# RH003_1.net
KiCad netlist of a schematic drawn in EAGLE
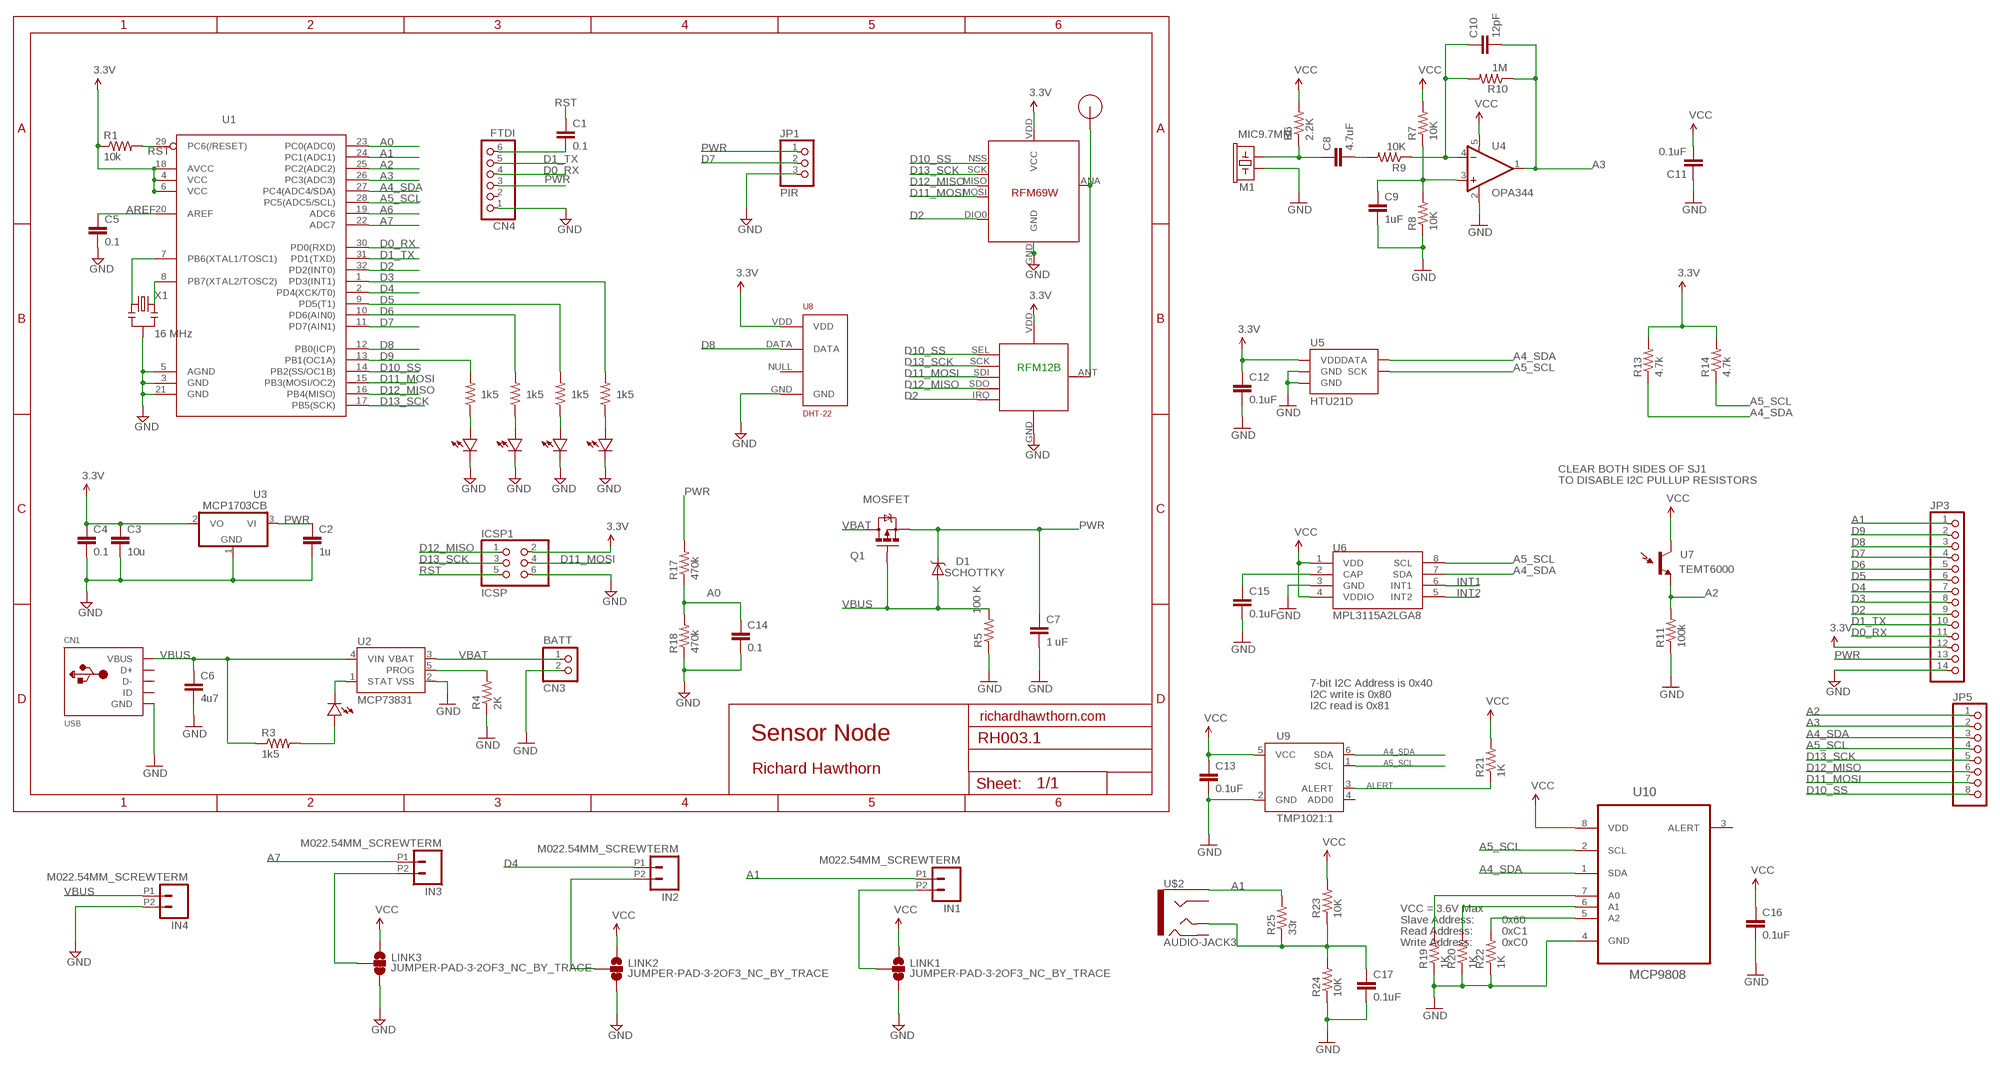
[diagram p0: schematic, sheet 1]

(export (version "E")
  (design (tool "Eeschema 10.0.6"))
  (components
    (comp (ref "C1")
      (value "0.1")
      (footprint "eagle-import:0603-CAP")
      (libsource (lib "eagle-import") (part "CAP0603-CAP"))
    )
    (comp (ref "C2")
      (value "1u")
      (footprint "eagle-import:0603-CAP")
      (libsource (lib "eagle-import") (part "CAP0603-CAP"))
    )
    (comp (ref "C3")
      (value "10u")
      (footprint "eagle-import:0805-CAP")
      (libsource (lib "eagle-import") (part "CAP0805-CAP"))
    )
    (comp (ref "C4")
      (value "0.1")
      (footprint "eagle-import:0603-CAP")
      (libsource (lib "eagle-import") (part "CAP0603-CAP"))
    )
    (comp (ref "C5")
      (value "0.1")
      (footprint "eagle-import:0603-CAP")
      (libsource (lib "eagle-import") (part "CAP0603-CAP"))
    )
    (comp (ref "C6")
      (value "4u7")
      (footprint "eagle-import:0603-CAP")
      (libsource (lib "eagle-import") (part "SparkFun_CAP0603-CAP"))
    )
    (comp (ref "C7")
      (value "1 uF")
      (footprint "eagle-import:0805")
      (libsource (lib "eagle-import") (part "SparkFun-Capacitors_CAP0805"))
    )
    (comp (ref "C8")
      (value "4.7uF")
      (footprint "eagle-import:0805")
      (libsource (lib "eagle-import") (part "SparkFun_CAP0805"))
    )
    (comp (ref "C9")
      (value "1uF")
      (footprint "eagle-import:0805")
      (libsource (lib "eagle-import") (part "SparkFun_CAP0805"))
    )
    (comp (ref "C10")
      (value "12pF")
      (footprint "eagle-import:0805")
      (libsource (lib "eagle-import") (part "SparkFun_CAP0805"))
    )
    (comp (ref "C11")
      (value "0.1uF")
      (footprint "eagle-import:0805")
      (libsource (lib "eagle-import") (part "SparkFun_CAP0805"))
    )
    (comp (ref "C12")
      (value "0.1uF")
      (footprint "eagle-import:0805")
      (libsource (lib "eagle-import") (part "SparkFun_CAP0805"))
    )
    (comp (ref "C13")
      (value "0.1uF")
      (footprint "eagle-import:0603-CAP")
      (libsource (lib "eagle-import") (part "SparkFun_CAP0603-CAP"))
    )
    (comp (ref "C14")
      (value "0.1")
      (footprint "eagle-import:0603-CAP")
      (libsource (lib "eagle-import") (part "CAP0603-CAP"))
    )
    (comp (ref "C15")
      (value "0.1uF")
      (footprint "eagle-import:0805")
      (libsource (lib "eagle-import") (part "SparkFun_CAP0805"))
    )
    (comp (ref "C16")
      (value "0.1uF")
      (footprint "eagle-import:0603-CAP")
      (libsource (lib "eagle-import") (part "SparkFun_CAP0603-CAP"))
    )
    (comp (ref "C17")
      (value "0.1uF")
      (footprint "eagle-import:0603-CAP")
      (libsource (lib "eagle-import") (part "SparkFun_CAP0603-CAP"))
    )
    (comp (ref "CN1")
      (value "USB")
      (footprint "eagle-import:USB-MINIB")
      (libsource (lib "eagle-import") (part "USBMINIB"))
    )
    (comp (ref "CN3")
      (value "BATT")
      (footprint "eagle-import:JST-PH-2-SMT-RA")
      (libsource (lib "eagle-import") (part "JST_2PIN-SMT-RA"))
    )
    (comp (ref "CN4")
      (value "FTDI")
      (footprint "eagle-import:1X06")
      (libsource (lib "eagle-import") (part "PINHD-1X6"))
    )
    (comp (ref "D1")
      (value "SCHOTTKY")
      (footprint "eagle-import:SMA-DIODE")
      (libsource (lib "eagle-import") (part "DIODE-SCHOTTKY_"))
    )
    (comp (ref "ICSP1")
      (value "ICSP")
      (footprint "eagle-import:2X03")
      (libsource (lib "eagle-import") (part "PINHD-2X3"))
    )
    (comp (ref "IN1")
      (value "M022.54MM_SCREWTERM")
      (footprint "eagle-import:1X02_2.54_SCREWTERM")
      (libsource (lib "eagle-import") (part "M022.54MM_SCREWTERM"))
    )
    (comp (ref "IN2")
      (value "M022.54MM_SCREWTERM")
      (footprint "eagle-import:1X02_2.54_SCREWTERM")
      (libsource (lib "eagle-import") (part "M022.54MM_SCREWTERM"))
    )
    (comp (ref "IN3")
      (value "M022.54MM_SCREWTERM")
      (footprint "eagle-import:1X02_2.54_SCREWTERM")
      (libsource (lib "eagle-import") (part "M022.54MM_SCREWTERM"))
    )
    (comp (ref "IN4")
      (value "M022.54MM_SCREWTERM")
      (footprint "eagle-import:1X02_2.54_SCREWTERM")
      (libsource (lib "eagle-import") (part "M022.54MM_SCREWTERM"))
    )
    (comp (ref "JP1")
      (value "PIR")
      (footprint "eagle-import:1X03")
      (libsource (lib "eagle-import") (part "PINHD-1X3"))
    )
    (comp (ref "JP3")
      (value "PINHD-1X14")
      (footprint "eagle-import:1X14")
      (libsource (lib "eagle-import") (part "PINHD-1X14"))
    )
    (comp (ref "JP5")
      (value "PINHD-1X8")
      (footprint "eagle-import:1X08")
      (libsource (lib "eagle-import") (part "PINHD-1X8"))
    )
    (comp (ref "LED1")
      (value "LED0603")
      (footprint "eagle-import:0603-LED")
      (libsource (lib "eagle-import") (part "LED0603"))
    )
    (comp (ref "LED2")
      (value "LED0603")
      (footprint "eagle-import:0603-LED")
      (libsource (lib "eagle-import") (part "LED0603"))
    )
    (comp (ref "LED3")
      (value "LED0603")
      (footprint "eagle-import:0603-LED")
      (libsource (lib "eagle-import") (part "LED0603"))
    )
    (comp (ref "LED4")
      (value "LED0603")
      (footprint "eagle-import:0603-LED")
      (libsource (lib "eagle-import") (part "LED0603"))
    )
    (comp (ref "LED5")
      (value "LED0603")
      (footprint "eagle-import:0603-LED")
      (libsource (lib "eagle-import") (part "LED0603"))
    )
    (comp (ref "LINK1")
      (value "JUMPER-PAD-3-2OF3_NC_BY_TRACE")
      (footprint "eagle-import:PAD-JUMPER-3-2OF3_NC_BY_TRACE_YES_SILK_FULL_BOX")
      (libsource (lib "eagle-import") (part "JUMPER-PAD-3-2OF3_NC_BY_TRACE"))
    )
    (comp (ref "LINK2")
      (value "JUMPER-PAD-3-2OF3_NC_BY_TRACE")
      (footprint "eagle-import:PAD-JUMPER-3-2OF3_NC_BY_TRACE_YES_SILK_FULL_BOX")
      (libsource (lib "eagle-import") (part "JUMPER-PAD-3-2OF3_NC_BY_TRACE"))
    )
    (comp (ref "LINK3")
      (value "JUMPER-PAD-3-2OF3_NC_BY_TRACE")
      (footprint "eagle-import:PAD-JUMPER-3-2OF3_NC_BY_TRACE_YES_SILK_FULL_BOX")
      (libsource (lib "eagle-import") (part "JUMPER-PAD-3-2OF3_NC_BY_TRACE"))
    )
    (comp (ref "M1")
      (value "MIC9.7MM")
      (footprint "eagle-import:MIC-9.7MM")
      (libsource (lib "eagle-import") (part "MIC9.7MM"))
    )
    (comp (ref "Q1")
      (value "MOSFET")
      (footprint "eagle-import:SOT23-3")
      (libsource (lib "eagle-import") (part "MOSFET-PCHANNELSMD"))
    )
    (comp (ref "R1")
      (value "10k")
      (footprint "eagle-import:0603-RES")
      (libsource (lib "eagle-import") (part "RESISTOR0603-RES"))
    )
    (comp (ref "R2")
      (value "1k5")
      (footprint "eagle-import:0805")
      (libsource (lib "eagle-import") (part "RESISTOR0805"))
    )
    (comp (ref "R3")
      (value "1k5")
      (footprint "eagle-import:0603-RES")
      (libsource (lib "eagle-import") (part "RESISTOR0603-RES"))
    )
    (comp (ref "R4")
      (value "2K")
      (footprint "eagle-import:0603-RES")
      (libsource (lib "eagle-import") (part "RESISTOR0603-RES"))
    )
    (comp (ref "R5")
      (value "100 K")
      (footprint "eagle-import:0805")
      (libsource (lib "eagle-import") (part "SparkFun-Resistors_RESISTOR0805-RES"))
    )
    (comp (ref "R6")
      (value "2.2K")
      (footprint "eagle-import:0805")
      (libsource (lib "eagle-import") (part "SparkFun_RESISTOR0805-RES"))
    )
    (comp (ref "R7")
      (value "10K")
      (footprint "eagle-import:0805")
      (libsource (lib "eagle-import") (part "SparkFun_RESISTOR0805-RES"))
    )
    (comp (ref "R8")
      (value "10K")
      (footprint "eagle-import:0805")
      (libsource (lib "eagle-import") (part "SparkFun_RESISTOR0805-RES"))
    )
    (comp (ref "R9")
      (value "10K")
      (footprint "eagle-import:0805")
      (libsource (lib "eagle-import") (part "SparkFun_RESISTOR0805-RES"))
    )
    (comp (ref "R10")
      (value "1M")
      (footprint "eagle-import:0805")
      (libsource (lib "eagle-import") (part "SparkFun_RESISTOR0805-RES"))
    )
    (comp (ref "R11")
      (value "100k")
      (footprint "eagle-import:0603-RES")
      (libsource (lib "eagle-import") (part "SparkFun_RESISTOR0603-RES"))
    )
    (comp (ref "R12")
      (value "1k5")
      (footprint "eagle-import:0805")
      (libsource (lib "eagle-import") (part "RESISTOR0805"))
    )
    (comp (ref "R13")
      (value "4.7k")
      (footprint "eagle-import:0805")
      (libsource (lib "eagle-import") (part "SparkFun_RESISTOR0805-RES"))
    )
    (comp (ref "R14")
      (value "4.7k")
      (footprint "eagle-import:0805")
      (libsource (lib "eagle-import") (part "SparkFun_RESISTOR0805-RES"))
    )
    (comp (ref "R15")
      (value "1k5")
      (footprint "eagle-import:0805")
      (libsource (lib "eagle-import") (part "RESISTOR0805"))
    )
    (comp (ref "R16")
      (value "1k5")
      (footprint "eagle-import:0805")
      (libsource (lib "eagle-import") (part "RESISTOR0805"))
    )
    (comp (ref "R17")
      (value "470k")
      (footprint "eagle-import:0603-RES")
      (libsource (lib "eagle-import") (part "RESISTOR0603-RES"))
    )
    (comp (ref "R18")
      (value "470k")
      (footprint "eagle-import:0603-RES")
      (libsource (lib "eagle-import") (part "RESISTOR0603-RES"))
    )
    (comp (ref "R19")
      (value "1K")
      (footprint "eagle-import:0603-RES")
      (libsource (lib "eagle-import") (part "SparkFun_RESISTOR0603-RES"))
    )
    (comp (ref "R20")
      (value "1K")
      (footprint "eagle-import:0603-RES")
      (libsource (lib "eagle-import") (part "SparkFun_RESISTOR0603-RES"))
    )
    (comp (ref "R21")
      (value "1K")
      (footprint "eagle-import:0603-RES")
      (libsource (lib "eagle-import") (part "SparkFun_RESISTOR0603-RES"))
    )
    (comp (ref "R22")
      (value "1K")
      (footprint "eagle-import:0603-RES")
      (libsource (lib "eagle-import") (part "SparkFun_RESISTOR0603-RES"))
    )
    (comp (ref "R23")
      (value "10K")
      (footprint "eagle-import:0603-RES")
      (libsource (lib "eagle-import") (part "SparkFun_RESISTOR0603-RES"))
    )
    (comp (ref "R24")
      (value "10K")
      (footprint "eagle-import:0603-RES")
      (libsource (lib "eagle-import") (part "SparkFun_RESISTOR0603-RES"))
    )
    (comp (ref "R25")
      (value "33r")
      (footprint "eagle-import:0603-RES")
      (libsource (lib "eagle-import") (part "SparkFun_RESISTOR0603-RES"))
    )
    (comp (ref "RF1")
      (value "RFM12B")
      (footprint "eagle-import:RFM12B-MINPADS")
      (libsource (lib "eagle-import") (part "RFM12B_MINPADS"))
    )
    (comp (ref "RF2")
      (value "RFM69")
      (footprint "eagle-import:RFM69W-MINPADS")
      (libsource (lib "eagle-import") (part "RFM69"))
    )
    (comp (ref "U$1")
      (value "RFM12B_ANTENNA")
      (footprint "eagle-import:RFM12B-ANTENNA")
      (libsource (lib "eagle-import") (part "RFM12B_ANTENNA"))
    )
    (comp (ref "U$2")
      (value "AUDIO-JACK3")
      (footprint "eagle-import:AUDIO-JACK-TRRS-SMD")
      (libsource (lib "eagle-import") (part "AUDIO-JACK3"))
    )
    (comp (ref "U1")
      (value "ATMega-328")
      (footprint "eagle-import:TQFP32-08")
      (libsource (lib "eagle-import") (part "ATMEGA168/328TQFP32"))
    )
    (comp (ref "U2")
      (value "MCP73831")
      (footprint "eagle-import:SOT23-5")
      (libsource (lib "eagle-import") (part "MCP73831"))
    )
    (comp (ref "U3")
      (value "MCP1703CB")
      (footprint "eagle-import:SOT23")
      (libsource (lib "eagle-import") (part "MCP1703CB"))
    )
    (comp (ref "U4")
      (value "OPA344")
      (footprint "eagle-import:SOT23-5")
      (libsource (lib "eagle-import") (part "OPA344"))
    )
    (comp (ref "U5")
      (value "HTU21D")
      (footprint "eagle-import:HTU21D")
      (libsource (lib "eagle-import") (part "HTU21DSMD"))
    )
    (comp (ref "U6")
      (value "MPL3115A2LGA8")
      (footprint "eagle-import:LGA8")
      (libsource (lib "eagle-import") (part "MPL3115A2LGA8"))
    )
    (comp (ref "U7")
      (value "TEMT6000")
      (footprint "eagle-import:TEMT6000-SEN")
      (libsource (lib "eagle-import") (part "TEMT6000"))
    )
    (comp (ref "U8")
      (value "DHT-22")
      (footprint "eagle-import:RHT03_DHT-22_RA")
      (libsource (lib "eagle-import") (part "RHT03_DHT-22_AM2302RA"))
    )
    (comp (ref "U9")
      (value "TMP1021:1")
      (footprint "eagle-import:SOT563-2")
      (libsource (lib "eagle-import") (part "TMP1021{colon}1"))
    )
    (comp (ref "U10")
      (value "MCP9808")
      (footprint "eagle-import:SOP65P490X110-8N")
      (fields (field (name "MPN") "MCP9808-E/MS"))
      (libsource (lib "eagle-import") (part "MCP9808-E/MS"))
    )
    (comp (ref "X1")
      (value "16 MHz")
      (footprint "eagle-import:RESONATOR-SMD")
      (libsource (lib "eagle-import") (part "RESONATORSMD"))
    )
  )
  (nets
    (net (code "1") (name "/A0") (class "Default")
      (node (ref "C14") (pin "1") (pinfunction "1_1") (pintype "passive"))
      (node (ref "R17") (pin "1") (pinfunction "1_1") (pintype "passive"))
      (node (ref "R18") (pin "2") (pinfunction "2_2") (pintype "passive"))
      (node (ref "U1") (pin "23") (pinfunction "PC0(ADC0)_23") (pintype "bidirectional"))
    )
    (net (code "2") (name "/A1") (class "Default")
      (node (ref "IN1") (pin "P1") (pinfunction "1_P1") (pintype "passive"))
      (node (ref "JP3") (pin "1") (pinfunction "1_1") (pintype "passive"))
      (node (ref "R25") (pin "2") (pinfunction "2_2") (pintype "passive"))
      (node (ref "U$2") (pin "EARTH") (pinfunction "EARTH_EARTH") (pintype "bidirectional"))
      (node (ref "U1") (pin "24") (pinfunction "PC1(ADC1)_24") (pintype "bidirectional"))
    )
    (net (code "3") (name "/A2") (class "Default")
      (node (ref "JP5") (pin "1") (pinfunction "1_1") (pintype "passive"))
      (node (ref "R11") (pin "2") (pinfunction "2_2") (pintype "passive"))
      (node (ref "U1") (pin "25") (pinfunction "PC2(ADC2)_25") (pintype "bidirectional"))
      (node (ref "U7") (pin "EMITTER") (pinfunction "E1_EMITTER") (pintype "passive"))
    )
    (net (code "4") (name "/A3") (class "Default")
      (node (ref "C10") (pin "2") (pinfunction "2_2") (pintype "passive"))
      (node (ref "JP5") (pin "2") (pinfunction "2_2") (pintype "passive"))
      (node (ref "R10") (pin "1") (pinfunction "1_1") (pintype "passive"))
      (node (ref "U1") (pin "26") (pinfunction "PC3(ADC3)_26") (pintype "bidirectional"))
      (node (ref "U4") (pin "1") (pinfunction "OUT_1") (pintype "output"))
    )
    (net (code "5") (name "/A4_SDA") (class "Default")
      (node (ref "JP5") (pin "3") (pinfunction "3_3") (pintype "passive"))
      (node (ref "R13") (pin "1") (pinfunction "1_1") (pintype "passive"))
      (node (ref "U1") (pin "27") (pinfunction "PC4(ADC4/SDA)_27") (pintype "bidirectional"))
      (node (ref "U10") (pin "1") (pinfunction "SDA_1") (pintype "bidirectional"))
      (node (ref "U5") (pin "DATA") (pinfunction "DATA_DATA") (pintype "bidirectional"))
      (node (ref "U6") (pin "7") (pinfunction "SDA_7") (pintype "bidirectional"))
      (node (ref "U9") (pin "6") (pinfunction "SDA_6") (pintype "bidirectional"))
    )
    (net (code "6") (name "/A5_SCL") (class "Default")
      (node (ref "JP5") (pin "4") (pinfunction "4_4") (pintype "passive"))
      (node (ref "R14") (pin "1") (pinfunction "1_1") (pintype "passive"))
      (node (ref "U1") (pin "28") (pinfunction "PC5(ADC5/SCL)_28") (pintype "bidirectional"))
      (node (ref "U10") (pin "2") (pinfunction "SCL_2") (pintype "input"))
      (node (ref "U5") (pin "SCK") (pinfunction "SCK_SCK") (pintype "input"))
      (node (ref "U6") (pin "8") (pinfunction "SCL_8") (pintype "bidirectional"))
      (node (ref "U9") (pin "1") (pinfunction "SCL_1") (pintype "bidirectional"))
    )
    (net (code "7") (name "/A6") (class "Default")
      (node (ref "U1") (pin "19") (pinfunction "ADC6_19") (pintype "bidirectional"))
    )
    (net (code "8") (name "/A7") (class "Default")
      (node (ref "IN3") (pin "P1") (pinfunction "1_P1") (pintype "passive"))
      (node (ref "U1") (pin "22") (pinfunction "ADC7_22") (pintype "bidirectional"))
    )
    (net (code "9") (name "/ALERT") (class "Default")
      (node (ref "R21") (pin "1") (pinfunction "1_1") (pintype "passive"))
      (node (ref "U9") (pin "3") (pinfunction "ALERT_3") (pintype "bidirectional"))
    )
    (net (code "10") (name "/AREF") (class "Default")
      (node (ref "C5") (pin "1") (pinfunction "1_1") (pintype "passive"))
      (node (ref "U1") (pin "20") (pinfunction "AREF_20") (pintype "bidirectional"))
    )
    (net (code "11") (name "/D0_RX") (class "Default")
      (node (ref "CN4") (pin "4") (pinfunction "4_4") (pintype "passive"))
      (node (ref "JP3") (pin "11") (pinfunction "11_11") (pintype "passive"))
      (node (ref "U1") (pin "30") (pinfunction "PD0(RXD)_30") (pintype "bidirectional"))
    )
    (net (code "12") (name "/D1_TX") (class "Default")
      (node (ref "CN4") (pin "5") (pinfunction "5_5") (pintype "passive"))
      (node (ref "JP3") (pin "10") (pinfunction "10_10") (pintype "passive"))
      (node (ref "U1") (pin "31") (pinfunction "PD1(TXD)_31") (pintype "bidirectional"))
    )
    (net (code "13") (name "/D2") (class "Default")
      (node (ref "JP3") (pin "9") (pinfunction "9_9") (pintype "passive"))
      (node (ref "RF1") (pin "IRQ") (pinfunction "IRQ_IRQ") (pintype "bidirectional"))
      (node (ref "RF2") (pin "DIO0") (pinfunction "DIO0_DIO0") (pintype "open_collector"))
      (node (ref "U1") (pin "32") (pinfunction "PD2(INT0)_32") (pintype "bidirectional"))
    )
    (net (code "14") (name "/D3") (class "Default")
      (node (ref "JP3") (pin "8") (pinfunction "8_8") (pintype "passive"))
      (node (ref "R16") (pin "2") (pinfunction "2_2") (pintype "passive"))
      (node (ref "U1") (pin "1") (pinfunction "PD3(INT1)_1") (pintype "bidirectional"))
    )
    (net (code "15") (name "/D4") (class "Default")
      (node (ref "IN2") (pin "P1") (pinfunction "1_P1") (pintype "passive"))
      (node (ref "JP3") (pin "7") (pinfunction "7_7") (pintype "passive"))
      (node (ref "U1") (pin "2") (pinfunction "PD4(XCK/T0)_2") (pintype "bidirectional"))
    )
    (net (code "16") (name "/D5") (class "Default")
      (node (ref "JP3") (pin "6") (pinfunction "6_6") (pintype "passive"))
      (node (ref "R15") (pin "2") (pinfunction "2_2") (pintype "passive"))
      (node (ref "U1") (pin "9") (pinfunction "PD5(T1)_9") (pintype "bidirectional"))
    )
    (net (code "17") (name "/D6") (class "Default")
      (node (ref "JP3") (pin "5") (pinfunction "5_5") (pintype "passive"))
      (node (ref "R12") (pin "2") (pinfunction "2_2") (pintype "passive"))
      (node (ref "U1") (pin "10") (pinfunction "PD6(AIN0)_10") (pintype "bidirectional"))
    )
    (net (code "18") (name "/D7") (class "Default")
      (node (ref "JP1") (pin "2") (pinfunction "2_2") (pintype "passive"))
      (node (ref "JP3") (pin "4") (pinfunction "4_4") (pintype "passive"))
      (node (ref "U1") (pin "11") (pinfunction "PD7(AIN1)_11") (pintype "bidirectional"))
    )
    (net (code "19") (name "/D8") (class "Default")
      (node (ref "JP3") (pin "3") (pinfunction "3_3") (pintype "passive"))
      (node (ref "U1") (pin "12") (pinfunction "PB0(ICP)_12") (pintype "bidirectional"))
      (node (ref "U8") (pin "DATA") (pinfunction "DATA_DATA") (pintype "bidirectional"))
    )
    (net (code "20") (name "/D9") (class "Default")
      (node (ref "JP3") (pin "2") (pinfunction "2_2") (pintype "passive"))
      (node (ref "R2") (pin "2") (pinfunction "2_2") (pintype "passive"))
      (node (ref "U1") (pin "13") (pinfunction "PB1(OC1A)_13") (pintype "bidirectional"))
    )
    (net (code "21") (name "/D10_SS") (class "Default")
      (node (ref "JP5") (pin "8") (pinfunction "8_8") (pintype "passive"))
      (node (ref "RF1") (pin "SEL") (pinfunction "SEL_SEL") (pintype "bidirectional"))
      (node (ref "RF2") (pin "NSS") (pinfunction "SEL_NSS") (pintype "input"))
      (node (ref "U1") (pin "14") (pinfunction "PB2(SS/OC1B)_14") (pintype "bidirectional"))
    )
    (net (code "22") (name "/D11_MOSI") (class "Default")
      (node (ref "ICSP1") (pin "4") (pinfunction "4_4") (pintype "passive"))
      (node (ref "JP5") (pin "7") (pinfunction "7_7") (pintype "passive"))
      (node (ref "RF1") (pin "SDI") (pinfunction "SDI/MOSI_SDI") (pintype "bidirectional"))
      (node (ref "RF2") (pin "MOSI") (pinfunction "MOSI_MOSI") (pintype "output"))
      (node (ref "U1") (pin "15") (pinfunction "PB3(MOSI/OC2)_15") (pintype "bidirectional"))
    )
    (net (code "23") (name "/D12_MISO") (class "Default")
      (node (ref "ICSP1") (pin "1") (pinfunction "1_1") (pintype "passive"))
      (node (ref "JP5") (pin "6") (pinfunction "6_6") (pintype "passive"))
      (node (ref "RF1") (pin "SDO") (pinfunction "SDO/MISO_SDO") (pintype "bidirectional"))
      (node (ref "RF2") (pin "MISO") (pinfunction "MISO_MISO") (pintype "input"))
      (node (ref "U1") (pin "16") (pinfunction "PB4(MISO)_16") (pintype "bidirectional"))
    )
    (net (code "24") (name "/D13_SCK") (class "Default")
      (node (ref "ICSP1") (pin "3") (pinfunction "3_3") (pintype "passive"))
      (node (ref "JP5") (pin "5") (pinfunction "5_5") (pintype "passive"))
      (node (ref "RF1") (pin "SCK") (pinfunction "SCK_SCK") (pintype "bidirectional"))
      (node (ref "RF2") (pin "SCK") (pinfunction "SCK_SCK") (pintype "input"))
      (node (ref "U1") (pin "17") (pinfunction "PB5(SCK)_17") (pintype "bidirectional"))
    )
    (net (code "25") (name "/INT1") (class "Default")
      (node (ref "U6") (pin "6") (pinfunction "INT1_6") (pintype "bidirectional"))
    )
    (net (code "26") (name "/INT2") (class "Default")
      (node (ref "U6") (pin "5") (pinfunction "INT2_5") (pintype "bidirectional"))
    )
    (net (code "27") (name "/PWR") (class "Default")
      (node (ref "C2") (pin "1") (pinfunction "1_1") (pintype "passive"))
      (node (ref "C7") (pin "1") (pinfunction "1_1") (pintype "passive"))
      (node (ref "CN4") (pin "3") (pinfunction "3_3") (pintype "passive"))
      (node (ref "D1") (pin "C") (pinfunction "C_C") (pintype "passive"))
      (node (ref "JP1") (pin "1") (pinfunction "1_1") (pintype "passive"))
      (node (ref "JP3") (pin "13") (pinfunction "13_13") (pintype "passive"))
      (node (ref "Q1") (pin "2") (pinfunction "S_2") (pintype "passive"))
      (node (ref "R17") (pin "2") (pinfunction "2_2") (pintype "passive"))
      (node (ref "U3") (pin "3") (pinfunction "VI_3") (pintype "input"))
    )
    (net (code "28") (name "/RST") (class "Default")
      (node (ref "C1") (pin "1") (pinfunction "1_1") (pintype "passive"))
      (node (ref "ICSP1") (pin "5") (pinfunction "5_5") (pintype "passive"))
      (node (ref "R1") (pin "2") (pinfunction "2_2") (pintype "passive"))
      (node (ref "U1") (pin "29") (pinfunction "PC6(/RESET)_29") (pintype "bidirectional"))
    )
    (net (code "29") (name "/VBAT") (class "Default")
      (node (ref "CN3") (pin "1") (pinfunction "2_1") (pintype "passive"))
      (node (ref "Q1") (pin "3") (pinfunction "D_3") (pintype "passive"))
      (node (ref "U2") (pin "3") (pinfunction "VBAT_3") (pintype "power_in"))
    )
    (net (code "30") (name "/VBUS") (class "Default")
      (node (ref "C6") (pin "1") (pinfunction "1_1") (pintype "passive"))
      (node (ref "CN1") (pin "VBUS") (pinfunction "VBUS_VBUS") (pintype "power_in"))
      (node (ref "D1") (pin "A") (pinfunction "A_A") (pintype "passive"))
      (node (ref "IN4") (pin "P1") (pinfunction "1_P1") (pintype "passive"))
      (node (ref "Q1") (pin "1") (pinfunction "G_1") (pintype "passive"))
      (node (ref "R3") (pin "1") (pinfunction "1_1") (pintype "passive"))
      (node (ref "R5") (pin "2") (pinfunction "2_2") (pintype "passive"))
      (node (ref "U2") (pin "4") (pinfunction "VIN_4") (pintype "power_in"))
    )
    (net (code "31") (name "3.3V") (class "Default")
      (node (ref "C11") (pin "2") (pinfunction "2_2") (pintype "passive"))
      (node (ref "C12") (pin "1") (pinfunction "1_1") (pintype "passive"))
      (node (ref "C13") (pin "1") (pinfunction "1_1") (pintype "passive"))
      (node (ref "C16") (pin "1") (pinfunction "1_1") (pintype "passive"))
      (node (ref "C3") (pin "1") (pinfunction "1_1") (pintype "passive"))
      (node (ref "C4") (pin "1") (pinfunction "1_1") (pintype "passive"))
      (node (ref "ICSP1") (pin "2") (pinfunction "2_2") (pintype "passive"))
      (node (ref "JP3") (pin "12") (pinfunction "12_12") (pintype "passive"))
      (node (ref "LINK1") (pin "1") (pinfunction "1_1") (pintype "passive"))
      (node (ref "LINK2") (pin "1") (pinfunction "1_1") (pintype "passive"))
      (node (ref "LINK3") (pin "1") (pinfunction "1_1") (pintype "passive"))
      (node (ref "R1") (pin "1") (pinfunction "1_1") (pintype "passive"))
      (node (ref "R13") (pin "2") (pinfunction "2_2") (pintype "passive"))
      (node (ref "R14") (pin "2") (pinfunction "2_2") (pintype "passive"))
      (node (ref "R21") (pin "2") (pinfunction "2_2") (pintype "passive"))
      (node (ref "R23") (pin "2") (pinfunction "2_2") (pintype "passive"))
      (node (ref "R6") (pin "2") (pinfunction "2_2") (pintype "passive"))
      (node (ref "R7") (pin "2") (pinfunction "2_2") (pintype "passive"))
      (node (ref "RF1") (pin "VDD") (pinfunction "VDD_VDD") (pintype "bidirectional"))
      (node (ref "RF2") (pin "VDD") (pinfunction "VCC_VDD") (pintype "power_in"))
      (node (ref "U1") (pin "18") (pinfunction "AVCC_18") (pintype "bidirectional"))
      (node (ref "U1") (pin "4") (pinfunction "VCC_4") (pintype "bidirectional"))
      (node (ref "U1") (pin "6") (pinfunction "VCC_6") (pintype "bidirectional"))
      (node (ref "U10") (pin "8") (pinfunction "VDD_8") (pintype "power_in"))
      (node (ref "U3") (pin "2") (pinfunction "VO_2") (pintype "passive"))
      (node (ref "U4") (pin "5") (pinfunction "V+_5") (pintype "power_in"))
      (node (ref "U5") (pin "VDD") (pinfunction "VDD_VDD") (pintype "power_in"))
      (node (ref "U6") (pin "1") (pinfunction "VDD_1") (pintype "bidirectional"))
      (node (ref "U6") (pin "4") (pinfunction "VDDIO_4") (pintype "bidirectional"))
      (node (ref "U7") (pin "COLLECTOR") (pinfunction "C1_COLLECTOR") (pintype "passive"))
      (node (ref "U8") (pin "VDD") (pinfunction "VDD_VDD") (pintype "power_in"))
      (node (ref "U9") (pin "5") (pinfunction "VCC_5") (pintype "bidirectional"))
    )
    (net (code "32") (name "GND") (class "Default")
      (node (ref "C11") (pin "1") (pinfunction "1_1") (pintype "passive"))
      (node (ref "C12") (pin "2") (pinfunction "2_2") (pintype "passive"))
      (node (ref "C13") (pin "2") (pinfunction "2_2") (pintype "passive"))
      (node (ref "C14") (pin "2") (pinfunction "2_2") (pintype "passive"))
      (node (ref "C15") (pin "2") (pinfunction "2_2") (pintype "passive"))
      (node (ref "C16") (pin "2") (pinfunction "2_2") (pintype "passive"))
      (node (ref "C17") (pin "2") (pinfunction "2_2") (pintype "passive"))
      (node (ref "C2") (pin "2") (pinfunction "2_2") (pintype "passive"))
      (node (ref "C3") (pin "2") (pinfunction "2_2") (pintype "passive"))
      (node (ref "C4") (pin "2") (pinfunction "2_2") (pintype "passive"))
      (node (ref "C5") (pin "2") (pinfunction "2_2") (pintype "passive"))
      (node (ref "C6") (pin "2") (pinfunction "2_2") (pintype "passive"))
      (node (ref "C7") (pin "2") (pinfunction "2_2") (pintype "passive"))
      (node (ref "C9") (pin "2") (pinfunction "2_2") (pintype "passive"))
      (node (ref "CN1") (pin "GND") (pinfunction "GND_GND") (pintype "power_in"))
      (node (ref "CN3") (pin "2") (pinfunction "1_2") (pintype "passive"))
      (node (ref "CN4") (pin "1") (pinfunction "1_1") (pintype "passive"))
      (node (ref "ICSP1") (pin "6") (pinfunction "6_6") (pintype "passive"))
      (node (ref "IN4") (pin "P2") (pinfunction "2_P2") (pintype "passive"))
      (node (ref "JP1") (pin "3") (pinfunction "3_3") (pintype "passive"))
      (node (ref "JP3") (pin "14") (pinfunction "14_14") (pintype "passive"))
      (node (ref "LED2") (pin "MINUS") (pinfunction "MINUS_MINUS") (pintype "passive"))
      (node (ref "LED3") (pin "MINUS") (pinfunction "MINUS_MINUS") (pintype "passive"))
      (node (ref "LED4") (pin "MINUS") (pinfunction "MINUS_MINUS") (pintype "passive"))
      (node (ref "LED5") (pin "MINUS") (pinfunction "MINUS_MINUS") (pintype "passive"))
      (node (ref "LINK1") (pin "3") (pinfunction "3_3") (pintype "passive"))
      (node (ref "LINK2") (pin "3") (pinfunction "3_3") (pintype "passive"))
      (node (ref "LINK3") (pin "3") (pinfunction "3_3") (pintype "passive"))
      (node (ref "M1") (pin "2") (pinfunction "2_2") (pintype "passive"))
      (node (ref "R11") (pin "1") (pinfunction "1_1") (pintype "passive"))
      (node (ref "R18") (pin "1") (pinfunction "1_1") (pintype "passive"))
      (node (ref "R19") (pin "1") (pinfunction "1_1") (pintype "passive"))
      (node (ref "R20") (pin "1") (pinfunction "1_1") (pintype "passive"))
      (node (ref "R22") (pin "1") (pinfunction "1_1") (pintype "passive"))
      (node (ref "R24") (pin "1") (pinfunction "1_1") (pintype "passive"))
      (node (ref "R4") (pin "1") (pinfunction "1_1") (pintype "passive"))
      (node (ref "R5") (pin "1") (pinfunction "1_1") (pintype "passive"))
      (node (ref "R8") (pin "1") (pinfunction "1_1") (pintype "passive"))
      (node (ref "RF1") (pin "GND") (pinfunction "GND_GND") (pintype "bidirectional"))
      (node (ref "RF2") (pin "GND") (pinfunction "GND_GND") (pintype "power_in"))
      (node (ref "U1") (pin "21") (pinfunction "GND_21") (pintype "bidirectional"))
      (node (ref "U1") (pin "3") (pinfunction "GND_3") (pintype "bidirectional"))
      (node (ref "U1") (pin "5") (pinfunction "AGND_5") (pintype "bidirectional"))
      (node (ref "U10") (pin "4") (pinfunction "GND_4") (pintype "passive"))
      (node (ref "U2") (pin "2") (pinfunction "VSS_2") (pintype "power_in"))
      (node (ref "U3") (pin "1") (pinfunction "GND_1") (pintype "passive"))
      (node (ref "U4") (pin "2") (pinfunction "V-_2") (pintype "power_in"))
      (node (ref "U5") (pin "7") (pinfunction "GND_7") (pintype "power_in"))
      (node (ref "U5") (pin "GND") (pinfunction "GND_GND") (pintype "power_in"))
      (node (ref "U6") (pin "3") (pinfunction "GND_3") (pintype "bidirectional"))
      (node (ref "U8") (pin "GND") (pinfunction "GND_GND") (pintype "power_in"))
      (node (ref "U9") (pin "2") (pinfunction "GND_2") (pintype "bidirectional"))
      (node (ref "X1") (pin "2") (pinfunction "2_2") (pintype "passive"))
    )
    (net (code "33") (name "Net-(C1-Pad2)") (class "Default")
      (node (ref "C1") (pin "2") (pinfunction "2_2") (pintype "passive"))
      (node (ref "CN4") (pin "6") (pinfunction "6_6") (pintype "passive"))
    )
    (net (code "34") (name "Net-(C8-Pad1)") (class "Default")
      (node (ref "C8") (pin "1") (pinfunction "1_1") (pintype "passive"))
      (node (ref "M1") (pin "1") (pinfunction "1_1") (pintype "passive"))
      (node (ref "R6") (pin "1") (pinfunction "1_1") (pintype "passive"))
    )
    (net (code "35") (name "Net-(C8-Pad2)") (class "Default")
      (node (ref "C8") (pin "2") (pinfunction "2_2") (pintype "passive"))
      (node (ref "R9") (pin "2") (pinfunction "2_2") (pintype "passive"))
    )
    (net (code "36") (name "Net-(C17-Pad1)") (class "Default")
      (node (ref "C17") (pin "1") (pinfunction "1_1") (pintype "passive"))
      (node (ref "R23") (pin "1") (pinfunction "1_1") (pintype "passive"))
      (node (ref "R24") (pin "2") (pinfunction "2_2") (pintype "passive"))
      (node (ref "R25") (pin "1") (pinfunction "1_1") (pintype "passive"))
      (node (ref "U$2") (pin "TIP") (pinfunction "TIP_TIP") (pintype "bidirectional"))
    )
    (net (code "37") (name "Net-(IN1-2)") (class "Default")
      (node (ref "IN1") (pin "P2") (pinfunction "2_P2") (pintype "passive"))
      (node (ref "LINK1") (pin "2") (pinfunction "2_2") (pintype "passive"))
    )
    (net (code "38") (name "Net-(IN2-2)") (class "Default")
      (node (ref "IN2") (pin "P2") (pinfunction "2_P2") (pintype "passive"))
      (node (ref "LINK2") (pin "2") (pinfunction "2_2") (pintype "passive"))
    )
    (net (code "39") (name "Net-(IN3-2)") (class "Default")
      (node (ref "IN3") (pin "P2") (pinfunction "2_P2") (pintype "passive"))
      (node (ref "LINK3") (pin "2") (pinfunction "2_2") (pintype "passive"))
    )
    (net (code "40") (name "Net-(LED1-PadPLUS)") (class "Default")
      (node (ref "LED1") (pin "PLUS") (pinfunction "PLUS_PLUS") (pintype "passive"))
      (node (ref "R3") (pin "2") (pinfunction "2_2") (pintype "passive"))
    )
    (net (code "41") (name "Net-(LED2-PadPLUS)") (class "Default")
      (node (ref "LED2") (pin "PLUS") (pinfunction "PLUS_PLUS") (pintype "passive"))
      (node (ref "R2") (pin "1") (pinfunction "1_1") (pintype "passive"))
    )
    (net (code "42") (name "Net-(LED3-PadPLUS)") (class "Default")
      (node (ref "LED3") (pin "PLUS") (pinfunction "PLUS_PLUS") (pintype "passive"))
      (node (ref "R12") (pin "1") (pinfunction "1_1") (pintype "passive"))
    )
    (net (code "43") (name "Net-(LED4-PadPLUS)") (class "Default")
      (node (ref "LED4") (pin "PLUS") (pinfunction "PLUS_PLUS") (pintype "passive"))
      (node (ref "R15") (pin "1") (pinfunction "1_1") (pintype "passive"))
    )
    (net (code "44") (name "Net-(LED5-PadPLUS)") (class "Default")
      (node (ref "LED5") (pin "PLUS") (pinfunction "PLUS_PLUS") (pintype "passive"))
      (node (ref "R16") (pin "1") (pinfunction "1_1") (pintype "passive"))
    )
    (net (code "45") (name "Net-(RF2-ANT)") (class "Default")
      (node (ref "RF1") (pin "ANT") (pinfunction "ANT_ANT") (pintype "bidirectional"))
      (node (ref "RF2") (pin "ANA") (pinfunction "ANT_ANA") (pintype "passive"))
      (node (ref "U$1") (pin "P$1") (pinfunction "1_P$1") (pintype "bidirectional"))
    )
    (net (code "46") (name "Net-(U1-PB6(XTAL1{slash}TOSC1))") (class "Default")
      (node (ref "U1") (pin "7") (pinfunction "PB6(XTAL1/TOSC1)_7") (pintype "bidirectional"))
      (node (ref "X1") (pin "1") (pinfunction "1_1") (pintype "passive"))
    )
    (net (code "47") (name "Net-(U1-PB7(XTAL2{slash}TOSC2))") (class "Default")
      (node (ref "U1") (pin "8") (pinfunction "PB7(XTAL2/TOSC2)_8") (pintype "bidirectional"))
      (node (ref "X1") (pin "3") (pinfunction "3_3") (pintype "passive"))
    )
    (net (code "48") (name "Net-(U2-PROG)") (class "Default")
      (node (ref "R4") (pin "2") (pinfunction "2_2") (pintype "passive"))
      (node (ref "U2") (pin "5") (pinfunction "PROG_5") (pintype "input"))
    )
    (net (code "49") (name "Net-(U2-STAT)") (class "Default")
      (node (ref "LED1") (pin "MINUS") (pinfunction "MINUS_MINUS") (pintype "passive"))
      (node (ref "U2") (pin "1") (pinfunction "STAT_1") (pintype "output"))
    )
    (net (code "50") (name "Net-(U4-+IN)") (class "Default")
      (node (ref "C9") (pin "1") (pinfunction "1_1") (pintype "passive"))
      (node (ref "R7") (pin "1") (pinfunction "1_1") (pintype "passive"))
      (node (ref "R8") (pin "2") (pinfunction "2_2") (pintype "passive"))
      (node (ref "U4") (pin "3") (pinfunction "+IN_3") (pintype "input"))
    )
    (net (code "51") (name "Net-(U4--IN)") (class "Default")
      (node (ref "C10") (pin "1") (pinfunction "1_1") (pintype "passive"))
      (node (ref "R10") (pin "2") (pinfunction "2_2") (pintype "passive"))
      (node (ref "R9") (pin "1") (pinfunction "1_1") (pintype "passive"))
      (node (ref "U4") (pin "4") (pinfunction "-IN_4") (pintype "input"))
    )
    (net (code "52") (name "Net-(U6-CAP)") (class "Default")
      (node (ref "C15") (pin "1") (pinfunction "1_1") (pintype "passive"))
      (node (ref "U6") (pin "2") (pinfunction "CAP_2") (pintype "bidirectional"))
    )
    (net (code "53") (name "Net-(U10-A0)") (class "Default")
      (node (ref "R19") (pin "2") (pinfunction "2_2") (pintype "passive"))
      (node (ref "U10") (pin "7") (pinfunction "A0_7") (pintype "input"))
    )
    (net (code "54") (name "Net-(U10-A1)") (class "Default")
      (node (ref "R20") (pin "2") (pinfunction "2_2") (pintype "passive"))
      (node (ref "U10") (pin "6") (pinfunction "A1_6") (pintype "input"))
    )
    (net (code "55") (name "Net-(U10-A2)") (class "Default")
      (node (ref "R22") (pin "2") (pinfunction "2_2") (pintype "passive"))
      (node (ref "U10") (pin "5") (pinfunction "A2_5") (pintype "input"))
    )
    (net (code "56") (name "unconnected-(CN1-PadD+)") (class "Default")
      (node (ref "CN1") (pin "D+") (pinfunction "D+_D+") (pintype "bidirectional"))
    )
    (net (code "57") (name "unconnected-(CN1-PadD-)") (class "Default")
      (node (ref "CN1") (pin "D-") (pinfunction "D-_D-") (pintype "bidirectional"))
    )
    (net (code "58") (name "unconnected-(CN1-PadID)") (class "Default")
      (node (ref "CN1") (pin "ID") (pinfunction "ID_ID") (pintype "bidirectional"))
    )
    (net (code "59") (name "unconnected-(CN4-Pad2)") (class "Default")
      (node (ref "CN4") (pin "2") (pinfunction "2_2") (pintype "passive"))
    )
    (net (code "60") (name "unconnected-(U$2-PadRING1)") (class "Default")
      (node (ref "U$2") (pin "RING1") (pinfunction "RING1_RING1") (pintype "bidirectional"))
    )
    (net (code "61") (name "unconnected-(U$2-PadRING2)") (class "Default")
      (node (ref "U$2") (pin "RING2") (pinfunction "RING2_RING2") (pintype "bidirectional"))
    )
    (net (code "62") (name "unconnected-(U8-PadNULL)") (class "Default")
      (node (ref "U8") (pin "NULL") (pinfunction "NULL_NULL") (pintype "no_connect"))
    )
    (net (code "63") (name "unconnected-(U9-ADD0-Pad4)") (class "Default")
      (node (ref "U9") (pin "4") (pinfunction "ADD0_4") (pintype "bidirectional"))
    )
    (net (code "64") (name "unconnected-(U10-ALERT-Pad3)") (class "Default")
      (node (ref "U10") (pin "3") (pinfunction "ALERT_3") (pintype "output"))
    )
  )
)
